# esp32-thing.net
KiCad netlist of a schematic drawn in EAGLE
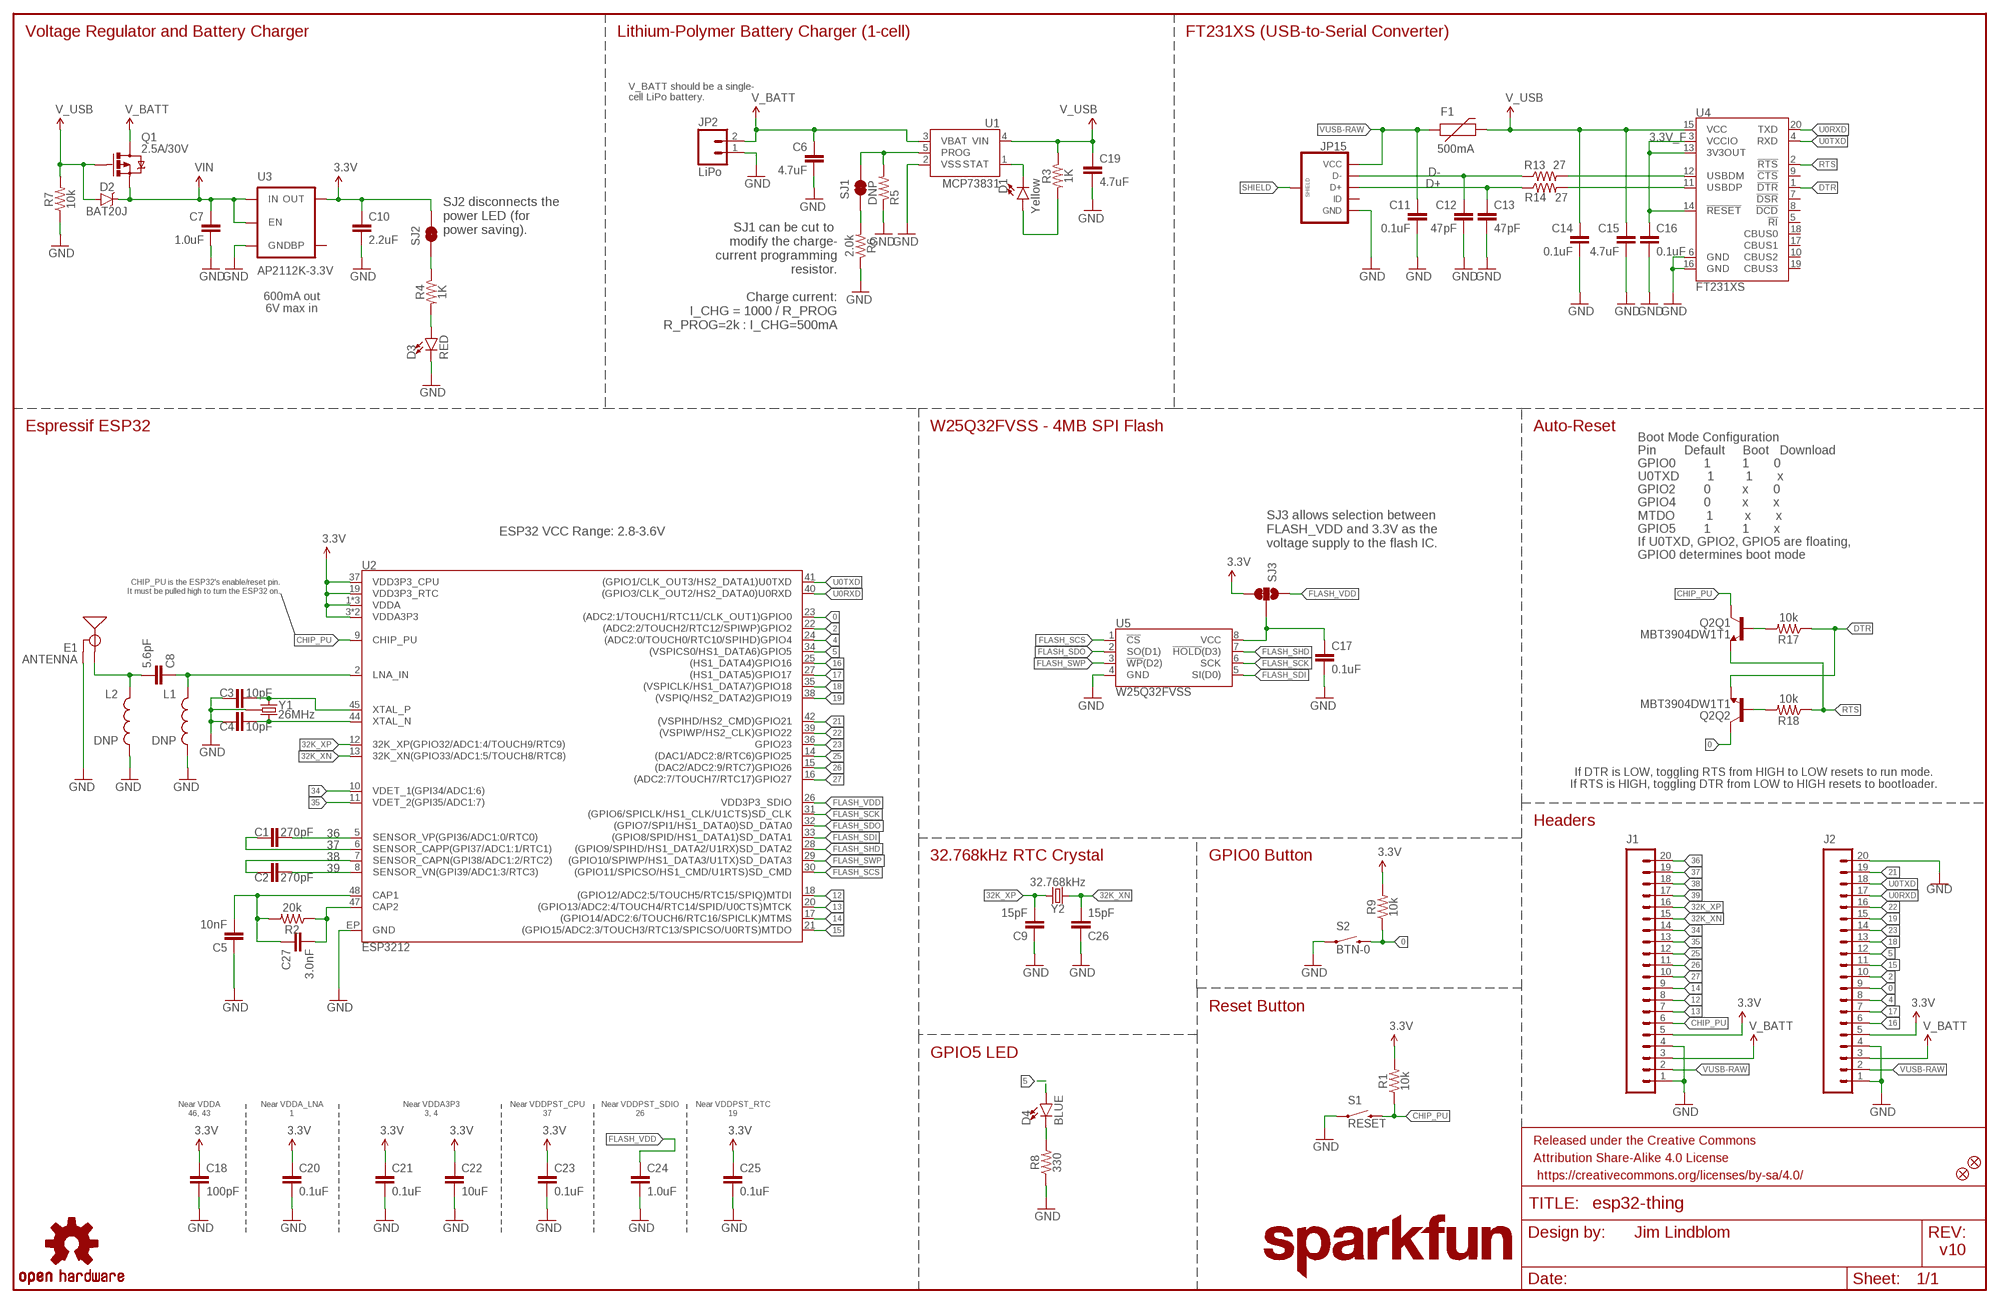
[diagram p0: schematic, sheet 1]

(export (version "E")
  (design (tool "Eeschema 10.0.6"))
  (components
    (comp (ref "C1")
      (value "270pF")
      (footprint "eagle-import:0603")
      (libsource (lib "eagle-import") (part "270PF-50V-5%(0603)"))
    )
    (comp (ref "C2")
      (value "270pF")
      (footprint "eagle-import:0603")
      (libsource (lib "eagle-import") (part "270PF-50V-5%(0603)"))
    )
    (comp (ref "C3")
      (value "10pF")
      (footprint "eagle-import:0603")
      (libsource (lib "eagle-import") (part "10PF-0603-50V-5%"))
    )
    (comp (ref "C4")
      (value "10pF")
      (footprint "eagle-import:0603")
      (libsource (lib "eagle-import") (part "10PF-0603-50V-5%"))
    )
    (comp (ref "C5")
      (value "10nF")
      (footprint "eagle-import:0603")
      (libsource (lib "eagle-import") (part "10NF-0603-50V-10%"))
    )
    (comp (ref "C6")
      (value "4.7uF")
      (footprint "eagle-import:0603")
      (libsource (lib "eagle-import") (part "4.7UF0603"))
    )
    (comp (ref "C7")
      (value "1.0uF")
      (footprint "eagle-import:0805")
      (libsource (lib "eagle-import") (part "1.0UF-0805-25V-(+80/-20%)"))
    )
    (comp (ref "C8")
      (value "5.6pF")
      (footprint "eagle-import:0603")
      (libsource (lib "eagle-import") (part "5.6PF-50V-5%(0603)"))
    )
    (comp (ref "C9")
      (value "15pF")
      (footprint "eagle-import:0603")
      (libsource (lib "eagle-import") (part "15PF-0603-50V-5%"))
    )
    (comp (ref "C10")
      (value "2.2uF")
      (footprint "eagle-import:0603")
      (libsource (lib "eagle-import") (part "2.2UF-0603-10V-20%"))
    )
    (comp (ref "C11")
      (value "0.1uF")
      (footprint "eagle-import:0603")
      (libsource (lib "eagle-import") (part "0.1UF-0603-25V-(+80/-20%)"))
    )
    (comp (ref "C12")
      (value "47pF")
      (footprint "eagle-import:0603")
      (libsource (lib "eagle-import") (part "47PF-0603-50V-5%"))
    )
    (comp (ref "C13")
      (value "47pF")
      (footprint "eagle-import:0603")
      (libsource (lib "eagle-import") (part "47PF-0603-50V-5%"))
    )
    (comp (ref "C14")
      (value "0.1uF")
      (footprint "eagle-import:0603")
      (libsource (lib "eagle-import") (part "0.1UF-0603-25V-(+80/-20%)"))
    )
    (comp (ref "C15")
      (value "4.7uF")
      (footprint "eagle-import:0603-CAP")
      (libsource (lib "eagle-import") (part "4.7UF-6.3V-10%(0603)0603"))
    )
    (comp (ref "C16")
      (value "0.1uF")
      (footprint "eagle-import:0603")
      (libsource (lib "eagle-import") (part "0.1UF-0603-25V-(+80/-20%)"))
    )
    (comp (ref "C17")
      (value "0.1uF")
      (footprint "eagle-import:0603")
      (libsource (lib "eagle-import") (part "0.1UF-0603-25V-(+80/-20%)"))
    )
    (comp (ref "C18")
      (value "100pF")
      (footprint "eagle-import:0603")
      (libsource (lib "eagle-import") (part "100PF-0603-50V-5%"))
    )
    (comp (ref "C19")
      (value "4.7uF")
      (footprint "eagle-import:0603")
      (libsource (lib "eagle-import") (part "4.7UF0603"))
    )
    (comp (ref "C20")
      (value "0.1uF")
      (footprint "eagle-import:0603")
      (libsource (lib "eagle-import") (part "0.1UF-0603-25V-(+80/-20%)"))
    )
    (comp (ref "C21")
      (value "0.1uF")
      (footprint "eagle-import:0603")
      (libsource (lib "eagle-import") (part "0.1UF-0603-25V-(+80/-20%)"))
    )
    (comp (ref "C22")
      (value "10uF")
      (footprint "eagle-import:0603")
      (libsource (lib "eagle-import") (part "10UF-0603-6.3V-20%"))
    )
    (comp (ref "C23")
      (value "0.1uF")
      (footprint "eagle-import:0603")
      (libsource (lib "eagle-import") (part "0.1UF-0603-25V-(+80/-20%)"))
    )
    (comp (ref "C24")
      (value "1.0uF")
      (footprint "eagle-import:0603")
      (libsource (lib "eagle-import") (part "1.0UF-0603-16V-10%"))
    )
    (comp (ref "C25")
      (value "0.1uF")
      (footprint "eagle-import:0603")
      (libsource (lib "eagle-import") (part "0.1UF-0603-25V-(+80/-20%)"))
    )
    (comp (ref "C26")
      (value "15pF")
      (footprint "eagle-import:0603")
      (libsource (lib "eagle-import") (part "15PF-0603-50V-5%"))
    )
    (comp (ref "C27")
      (value "3.0nF")
      (footprint "eagle-import:0603")
      (libsource (lib "eagle-import") (part "3.0NF-0603-50V-5%"))
    )
    (comp (ref "D1")
      (value "Yellow")
      (footprint "eagle-import:LED-0603")
      (libsource (lib "eagle-import") (part "LED-YELLOW0603"))
    )
    (comp (ref "D2")
      (value "BAT20J")
      (footprint "eagle-import:SOD-323")
      (libsource (lib "eagle-import") (part "DIODE-SCHOTTKY-BAT20J"))
    )
    (comp (ref "D3")
      (value "RED")
      (footprint "eagle-import:LED-0603")
      (libsource (lib "eagle-import") (part "LED-RED0603"))
    )
    (comp (ref "D4")
      (value "BLUE")
      (footprint "eagle-import:LED-0603")
      (libsource (lib "eagle-import") (part "LED-BLUE0603"))
    )
    (comp (ref "E1")
      (value "ANTENNA")
      (footprint "eagle-import:TRACE_ANTENNA_2.4GHZ_25.7MM_TUNED")
      (libsource (lib "eagle-import") (part "ANTENNATRACE-TUNED"))
    )
    (comp (ref "F1")
      (value "500mA")
      (footprint "eagle-import:PTC-1206")
      (libsource (lib "eagle-import") (part "PTCSMD"))
    )
    (comp (ref "FD1")
      (value "FIDUCIALUFIDUCIAL")
      (footprint "eagle-import:MICRO-FIDUCIAL")
      (libsource (lib "eagle-import") (part "FIDUCIALUFIDUCIAL"))
    )
    (comp (ref "FD2")
      (value "FIDUCIALUFIDUCIAL")
      (footprint "eagle-import:MICRO-FIDUCIAL")
      (libsource (lib "eagle-import") (part "FIDUCIALUFIDUCIAL"))
    )
    (comp (ref "FRAME1")
      (value "FRAME-LEDGER")
      (footprint "eagle-import:CREATIVE_COMMONS")
      (libsource (lib "eagle-import") (part "FRAME-LEDGER"))
    )
    (comp (ref "J1")
      (value "M20NOSILK")
      (footprint "eagle-import:1X20_NOSILK")
      (libsource (lib "eagle-import") (part "M20NOSILK"))
    )
    (comp (ref "J2")
      (value "M20NOSILK")
      (footprint "eagle-import:1X20_NOSILK")
      (libsource (lib "eagle-import") (part "M20NOSILK"))
    )
    (comp (ref "JP2")
      (value "LiPo")
      (footprint "eagle-import:JST-2-PTH")
      (libsource (lib "eagle-import") (part "M02JST-PTH-2"))
    )
    (comp (ref "JP15")
      (value "USB_MICROB_PLUGCONN-11752")
      (footprint "eagle-import:USB-B-MICRO-SMD_V03")
      (libsource (lib "eagle-import") (part "USB_MICROB_PLUGCONN-11752"))
    )
    (comp (ref "L1")
      (value "DNP")
      (footprint "eagle-import:0603")
      (libsource (lib "eagle-import") (part "INDUCTOR0603"))
    )
    (comp (ref "L2")
      (value "DNP")
      (footprint "eagle-import:0603")
      (libsource (lib "eagle-import") (part "INDUCTOR0603"))
    )
    (comp (ref "LOGO1")
      (value "SFE_LOGO_NAME.2_INCH")
      (footprint "eagle-import:SFE_LOGO_NAME_.2")
      (libsource (lib "eagle-import") (part "SFE_LOGO_NAME.2_INCH"))
    )
    (comp (ref "LOGO2")
      (value "OSHW-LOGOMINI")
      (footprint "eagle-import:OSHW-LOGO-MINI")
      (libsource (lib "eagle-import") (part "OSHW-LOGOMINI"))
    )
    (comp (ref "LOGO3")
      (value "SFE_LOGO_NAME.2_INCH")
      (footprint "eagle-import:SFE_LOGO_NAME_.2")
      (libsource (lib "eagle-import") (part "SFE_LOGO_NAME.2_INCH"))
    )
    (comp (ref "Q1")
      (value "2.5A/30V")
      (footprint "eagle-import:SOT23-3")
      (libsource (lib "eagle-import") (part "MOSFET-PCHANNELDMG2307L"))
    )
    (comp (ref "Q2")
      (value "MBT3904DW1T1")
      (footprint "eagle-import:SC70-6")
      (libsource (lib "eagle-import") (part "MBT3904DW1T1"))
    )
    (comp (ref "R1")
      (value "10k")
      (footprint "eagle-import:0603")
      (libsource (lib "eagle-import") (part "10KOHM-1/10W-1%(0603)0603"))
    )
    (comp (ref "R2")
      (value "20k")
      (footprint "eagle-import:0603")
      (libsource (lib "eagle-import") (part "20KOHM-0603-1/10W-1%"))
    )
    (comp (ref "R3")
      (value "1K")
      (footprint "eagle-import:0603")
      (libsource (lib "eagle-import") (part "1KOHM-1/10W-1%(0603)"))
    )
    (comp (ref "R4")
      (value "1K")
      (footprint "eagle-import:0603")
      (libsource (lib "eagle-import") (part "1KOHM-1/10W-1%(0603)"))
    )
    (comp (ref "R5")
      (value "DNP")
      (footprint "eagle-import:1_6W-RES")
      (libsource (lib "eagle-import") (part "RESISTORPTH-1/6W"))
    )
    (comp (ref "R6")
      (value "2.0k")
      (footprint "eagle-import:0603")
      (libsource (lib "eagle-import") (part "2.0KOHM1/10W5%(0603)"))
    )
    (comp (ref "R7")
      (value "10k")
      (footprint "eagle-import:0603")
      (libsource (lib "eagle-import") (part "10KOHM-0603-1/10W-1%"))
    )
    (comp (ref "R8")
      (value "330")
      (footprint "eagle-import:0603")
      (libsource (lib "eagle-import") (part "330OHM1/10W1%(0603)"))
    )
    (comp (ref "R9")
      (value "10k")
      (footprint "eagle-import:0603")
      (libsource (lib "eagle-import") (part "10KOHM-1/10W-1%(0603)0603"))
    )
    (comp (ref "R13")
      (value "27")
      (footprint "eagle-import:0603")
      (libsource (lib "eagle-import") (part "27OHM1/10W1%(0603)0603-RES"))
    )
    (comp (ref "R14")
      (value "27")
      (footprint "eagle-import:0603")
      (libsource (lib "eagle-import") (part "27OHM1/10W1%(0603)0603-RES"))
    )
    (comp (ref "R17")
      (value "10k")
      (footprint "eagle-import:0603")
      (libsource (lib "eagle-import") (part "10KOHM-0603-1/10W-1%"))
    )
    (comp (ref "R18")
      (value "10k")
      (footprint "eagle-import:0603")
      (libsource (lib "eagle-import") (part "10KOHM-0603-1/10W-1%"))
    )
    (comp (ref "S1")
      (value "RESET")
      (footprint "eagle-import:TACTILE_SWITCH_SMD_4.6X2.8MM")
      (libsource (lib "eagle-import") (part "SWITCH-MOMENTARY-2SMD-4.6X2.8MM"))
    )
    (comp (ref "S2")
      (value "BTN-0")
      (footprint "eagle-import:TACTILE_SWITCH_SMD_4.6X2.8MM")
      (libsource (lib "eagle-import") (part "SWITCH-MOMENTARY-2SMD-4.6X2.8MM"))
    )
    (comp (ref "SJ1")
      (value "JUMPER-PAD-2-NC_BY_TRACE")
      (footprint "eagle-import:PAD-JUMPER-2-NC_BY_TRACE_YES_SILK")
      (libsource (lib "eagle-import") (part "JUMPER-PAD-2-NC_BY_TRACE"))
    )
    (comp (ref "SJ2")
      (value "JUMPER-PAD-2-NC_BY_TRACE")
      (footprint "eagle-import:PAD-JUMPER-2-NC_BY_TRACE_YES_SILK")
      (libsource (lib "eagle-import") (part "JUMPER-PAD-2-NC_BY_TRACE"))
    )
    (comp (ref "SJ3")
      (value "JUMPER-PAD-3-2OF3_NC_BY_TRACE_SMALL")
      (footprint "eagle-import:PAD-JUMPER-3-2OF3_NC_BY_TRACE_YES_SILK_FULL_BOX")
      (libsource (lib "eagle-import") (part "JUMPER-PAD-3-2OF3_NC_BY_TRACE_SMALL"))
    )
    (comp (ref "U1")
      (value "MCP73831")
      (footprint "eagle-import:SOT23-5")
      (libsource (lib "eagle-import") (part "MCP73831"))
    )
    (comp (ref "U2")
      (value "ESP3212")
      (footprint "eagle-import:QFN48-0.4MM")
      (libsource (lib "eagle-import") (part "ESP3212"))
    )
    (comp (ref "U3")
      (value "AP2112K-3.3V")
      (footprint "eagle-import:SOT23-5")
      (libsource (lib "eagle-import") (part "V_REG_LDOSMD"))
    )
    (comp (ref "U4")
      (value "FT231XS")
      (footprint "eagle-import:SSOP20_L")
      (libsource (lib "eagle-import") (part "FT231XS"))
    )
    (comp (ref "U5")
      (value "W25Q32FVSS")
      (footprint "eagle-import:SOIC-8")
      (libsource (lib "eagle-import") (part "W25Q32FVSS"))
    )
    (comp (ref "Y1")
      (value "26MHz")
      (footprint "eagle-import:CRYSTAL-SMD-3.2X2.5")
      (libsource (lib "eagle-import") (part "CRYSTAL-GROUNDED3.2X2.5"))
    )
    (comp (ref "Y2")
      (value "32.768kHz")
      (footprint "eagle-import:CRYSTAL-SMD-3.2X1.5MM")
      (libsource (lib "eagle-import") (part "CRYSTAL-32.768KHZSMD-3.2X1.5"))
    )
  )
  (nets
    (net (code "1") (name "/3.3V_F") (class "Default")
      (node (ref "C16") (pin "1") (pinfunction "1_1") (pintype "passive"))
      (node (ref "U4") (pin "13") (pinfunction "3V3OUT_13") (pintype "bidirectional"))
      (node (ref "U4") (pin "14") (pinfunction "~{RESET}_14") (pintype "bidirectional"))
      (node (ref "U4") (pin "3") (pinfunction "VCCIO_3") (pintype "bidirectional"))
    )
    (net (code "2") (name "/D+") (class "Default")
      (node (ref "C13") (pin "1") (pinfunction "1_1") (pintype "passive"))
      (node (ref "JP15") (pin "D+") (pinfunction "D+_D+") (pintype "bidirectional"))
      (node (ref "R14") (pin "1") (pinfunction "1_1") (pintype "passive"))
    )
    (net (code "3") (name "/D-") (class "Default")
      (node (ref "C12") (pin "1") (pinfunction "1_1") (pintype "passive"))
      (node (ref "JP15") (pin "D-") (pinfunction "D-_D-") (pintype "bidirectional"))
      (node (ref "R13") (pin "1") (pinfunction "1_1") (pintype "passive"))
    )
    (net (code "4") (name "0") (class "Default")
      (node (ref "J2") (pin "9") (pinfunction "9_9") (pintype "passive"))
      (node (ref "Q2") (pin "6") (pinfunction "C_6") (pintype "passive"))
      (node (ref "R9") (pin "1") (pinfunction "1_1") (pintype "passive"))
      (node (ref "S2") (pin "3") (pinfunction "2_3") (pintype "passive"))
      (node (ref "S2") (pin "4") (pinfunction "2_4") (pintype "passive"))
      (node (ref "U2") (pin "23") (pinfunction "(ADC2:1/TOUCH1/RTC11/CLK_OUT1)GPIO0_23") (pintype "bidirectional"))
    )
    (net (code "5") (name "2") (class "Default")
      (node (ref "J2") (pin "10") (pinfunction "10_10") (pintype "passive"))
      (node (ref "U2") (pin "22") (pinfunction "(ADC2:2/TOUCH2/RTC12/SPIWP)GPIO2_22") (pintype "bidirectional"))
    )
    (net (code "6") (name "3.3V") (class "Default")
      (node (ref "C10") (pin "1") (pinfunction "1_1") (pintype "passive"))
      (node (ref "C18") (pin "1") (pinfunction "1_1") (pintype "passive"))
      (node (ref "C20") (pin "1") (pinfunction "1_1") (pintype "passive"))
      (node (ref "C21") (pin "1") (pinfunction "1_1") (pintype "passive"))
      (node (ref "C22") (pin "1") (pinfunction "1_1") (pintype "passive"))
      (node (ref "C23") (pin "1") (pinfunction "1_1") (pintype "passive"))
      (node (ref "C25") (pin "1") (pinfunction "1_1") (pintype "passive"))
      (node (ref "J1") (pin "5") (pinfunction "5_5") (pintype "passive"))
      (node (ref "J2") (pin "5") (pinfunction "5_5") (pintype "passive"))
      (node (ref "R1") (pin "2") (pinfunction "2_2") (pintype "passive"))
      (node (ref "R9") (pin "2") (pinfunction "2_2") (pintype "passive"))
      (node (ref "SJ2") (pin "2") (pinfunction "2_2") (pintype "passive"))
      (node (ref "SJ3") (pin "3") (pinfunction "3_3") (pintype "passive"))
      (node (ref "U2") (pin "1") (pinfunction "VDDA_1") (pintype "bidirectional"))
      (node (ref "U2") (pin "19") (pinfunction "VDD3P3_RTC_19") (pintype "bidirectional"))
      (node (ref "U2") (pin "3") (pinfunction "VDDA3P3_3") (pintype "bidirectional"))
      (node (ref "U2") (pin "37") (pinfunction "VDD3P3_CPU_37") (pintype "bidirectional"))
      (node (ref "U2") (pin "4") (pinfunction "VDDA3P3_4") (pintype "bidirectional"))
      (node (ref "U2") (pin "43") (pinfunction "VDDA_43") (pintype "bidirectional"))
      (node (ref "U2") (pin "46") (pinfunction "VDDA_46") (pintype "bidirectional"))
      (node (ref "U3") (pin "5") (pinfunction "OUT_5") (pintype "passive"))
    )
    (net (code "7") (name "4") (class "Default")
      (node (ref "J2") (pin "8") (pinfunction "8_8") (pintype "passive"))
      (node (ref "U2") (pin "24") (pinfunction "(ADC2:0/TOUCH0/RTC10/SPIHD)GPIO4_24") (pintype "bidirectional"))
    )
    (net (code "8") (name "5") (class "Default")
      (node (ref "D4") (pin "A") (pinfunction "A_A") (pintype "passive"))
      (node (ref "J2") (pin "12") (pinfunction "12_12") (pintype "passive"))
      (node (ref "U2") (pin "34") (pinfunction "(VSPICS0/HS1_DATA6)GPIO5_34") (pintype "bidirectional"))
    )
    (net (code "9") (name "12") (class "Default")
      (node (ref "J1") (pin "8") (pinfunction "8_8") (pintype "passive"))
      (node (ref "U2") (pin "18") (pinfunction "(GPIO12/ADC2:5/TOUCH5/RTC15/SPIQ)MTDI_18") (pintype "bidirectional"))
    )
    (net (code "10") (name "13") (class "Default")
      (node (ref "J1") (pin "7") (pinfunction "7_7") (pintype "passive"))
      (node (ref "U2") (pin "20") (pinfunction "(GPIO13/ADC2:4/TOUCH4/RTC14/SPID/U0CTS)MTCK_20") (pintype "bidirectional"))
    )
    (net (code "11") (name "14") (class "Default")
      (node (ref "J1") (pin "9") (pinfunction "9_9") (pintype "passive"))
      (node (ref "U2") (pin "17") (pinfunction "(GPIO14/ADC2:6/TOUCH6/RTC16/SPICLK)MTMS_17") (pintype "bidirectional"))
    )
    (net (code "12") (name "15") (class "Default")
      (node (ref "J2") (pin "11") (pinfunction "11_11") (pintype "passive"))
      (node (ref "U2") (pin "21") (pinfunction "(GPIO15/ADC2:3/TOUCH3/RTC13/SPICSO/U0RTS)MTDO_21") (pintype "bidirectional"))
    )
    (net (code "13") (name "16") (class "Default")
      (node (ref "J2") (pin "6") (pinfunction "6_6") (pintype "passive"))
      (node (ref "U2") (pin "25") (pinfunction "(HS1_DATA4)GPIO16_25") (pintype "bidirectional"))
    )
    (net (code "14") (name "17") (class "Default")
      (node (ref "J2") (pin "7") (pinfunction "7_7") (pintype "passive"))
      (node (ref "U2") (pin "27") (pinfunction "(HS1_DATA5)GPIO17_27") (pintype "bidirectional"))
    )
    (net (code "15") (name "18") (class "Default")
      (node (ref "J2") (pin "13") (pinfunction "13_13") (pintype "passive"))
      (node (ref "U2") (pin "35") (pinfunction "(VSPICLK/HS1_DATA7)GPIO18_35") (pintype "bidirectional"))
    )
    (net (code "16") (name "19") (class "Default")
      (node (ref "J2") (pin "15") (pinfunction "15_15") (pintype "passive"))
      (node (ref "U2") (pin "38") (pinfunction "(VSPIQ/HS2_DATA2)GPIO19_38") (pintype "bidirectional"))
    )
    (net (code "17") (name "21") (class "Default")
      (node (ref "J2") (pin "19") (pinfunction "19_19") (pintype "passive"))
      (node (ref "U2") (pin "42") (pinfunction "(VSPIHD/HS2_CMD)GPIO21_42") (pintype "bidirectional"))
    )
    (net (code "18") (name "22") (class "Default")
      (node (ref "J2") (pin "16") (pinfunction "16_16") (pintype "passive"))
      (node (ref "U2") (pin "39") (pinfunction "(VSPIWP/HS2_CLK)GPIO22_39") (pintype "bidirectional"))
    )
    (net (code "19") (name "23") (class "Default")
      (node (ref "J2") (pin "14") (pinfunction "14_14") (pintype "passive"))
      (node (ref "U2") (pin "36") (pinfunction "GPIO23_36") (pintype "bidirectional"))
    )
    (net (code "20") (name "25") (class "Default")
      (node (ref "J1") (pin "12") (pinfunction "12_12") (pintype "passive"))
      (node (ref "U2") (pin "14") (pinfunction "(DAC1/ADC2:8/RTC6)GPIO25_14") (pintype "bidirectional"))
    )
    (net (code "21") (name "26") (class "Default")
      (node (ref "J1") (pin "11") (pinfunction "11_11") (pintype "passive"))
      (node (ref "U2") (pin "15") (pinfunction "(DAC2/ADC2:9/RTC7)GPIO26_15") (pintype "bidirectional"))
    )
    (net (code "22") (name "27") (class "Default")
      (node (ref "J1") (pin "10") (pinfunction "10_10") (pintype "passive"))
      (node (ref "U2") (pin "16") (pinfunction "(ADC2:7/TOUCH7/RTC17)GPIO27_16") (pintype "bidirectional"))
    )
    (net (code "23") (name "32K_XN") (class "Default")
      (node (ref "C26") (pin "2") (pinfunction "2_2") (pintype "passive"))
      (node (ref "J1") (pin "15") (pinfunction "15_15") (pintype "passive"))
      (node (ref "U2") (pin "13") (pinfunction "32K_XN(GPIO33/ADC1:5/TOUCH8/RTC8)_13") (pintype "bidirectional"))
      (node (ref "Y2") (pin "P$2") (pinfunction "2_P$2") (pintype "passive"))
    )
    (net (code "24") (name "32K_XP") (class "Default")
      (node (ref "C9") (pin "2") (pinfunction "2_2") (pintype "passive"))
      (node (ref "J1") (pin "16") (pinfunction "16_16") (pintype "passive"))
      (node (ref "U2") (pin "12") (pinfunction "32K_XP(GPIO32/ADC1:4/TOUCH9/RTC9)_12") (pintype "bidirectional"))
      (node (ref "Y2") (pin "P$1") (pinfunction "1_P$1") (pintype "passive"))
    )
    (net (code "25") (name "34") (class "Default")
      (node (ref "J1") (pin "14") (pinfunction "14_14") (pintype "passive"))
      (node (ref "U2") (pin "10") (pinfunction "VDET_1(GPI34/ADC1:6)_10") (pintype "bidirectional"))
    )
    (net (code "26") (name "35") (class "Default")
      (node (ref "J1") (pin "13") (pinfunction "13_13") (pintype "passive"))
      (node (ref "U2") (pin "11") (pinfunction "VDET_2(GPI35/ADC1:7)_11") (pintype "bidirectional"))
    )
    (net (code "27") (name "36") (class "Default")
      (node (ref "C1") (pin "2") (pinfunction "2_2") (pintype "passive"))
      (node (ref "J1") (pin "20") (pinfunction "20_20") (pintype "passive"))
      (node (ref "U2") (pin "5") (pinfunction "SENSOR_VP(GPI36/ADC1:0/RTC0)_5") (pintype "bidirectional"))
    )
    (net (code "28") (name "37") (class "Default")
      (node (ref "C1") (pin "1") (pinfunction "1_1") (pintype "passive"))
      (node (ref "J1") (pin "19") (pinfunction "19_19") (pintype "passive"))
      (node (ref "U2") (pin "6") (pinfunction "SENSOR_CAPP(GPI37/ADC1:1/RTC1)_6") (pintype "bidirectional"))
    )
    (net (code "29") (name "38") (class "Default")
      (node (ref "C2") (pin "1") (pinfunction "1_1") (pintype "passive"))
      (node (ref "J1") (pin "18") (pinfunction "18_18") (pintype "passive"))
      (node (ref "U2") (pin "7") (pinfunction "SENSOR_CAPN(GPI38/ADC1:2/RTC2)_7") (pintype "bidirectional"))
    )
    (net (code "30") (name "39") (class "Default")
      (node (ref "C2") (pin "2") (pinfunction "2_2") (pintype "passive"))
      (node (ref "J1") (pin "17") (pinfunction "17_17") (pintype "passive"))
      (node (ref "U2") (pin "8") (pinfunction "SENSOR_VN(GPI39/ADC1:3/RTC3)_8") (pintype "bidirectional"))
    )
    (net (code "31") (name "CHIP_PU") (class "Default")
      (node (ref "J1") (pin "6") (pinfunction "6_6") (pintype "passive"))
      (node (ref "Q2") (pin "3") (pinfunction "C_3") (pintype "passive"))
      (node (ref "R1") (pin "1") (pinfunction "1_1") (pintype "passive"))
      (node (ref "S1") (pin "3") (pinfunction "2_3") (pintype "passive"))
      (node (ref "S1") (pin "4") (pinfunction "2_4") (pintype "passive"))
      (node (ref "U2") (pin "9") (pinfunction "CHIP_PU_9") (pintype "bidirectional"))
    )
    (net (code "32") (name "DTR") (class "Default")
      (node (ref "Q2") (pin "1") (pinfunction "E_1") (pintype "passive"))
      (node (ref "R17") (pin "1") (pinfunction "1_1") (pintype "passive"))
      (node (ref "U4") (pin "1") (pinfunction "~{DTR}_1") (pintype "bidirectional"))
    )
    (net (code "33") (name "FLASH_SCK") (class "Default")
      (node (ref "U2") (pin "31") (pinfunction "(GPIO6/SPICLK/HS1_CLK/U1CTS)SD_CLK_31") (pintype "bidirectional"))
      (node (ref "U5") (pin "6") (pinfunction "SCK_6") (pintype "bidirectional"))
    )
    (net (code "34") (name "FLASH_SCS") (class "Default")
      (node (ref "U2") (pin "30") (pinfunction "(GPIO11/SPICSO/HS1_CMD/U1RTS)SD_CMD_30") (pintype "bidirectional"))
      (node (ref "U5") (pin "1") (pinfunction "~{CS}_1") (pintype "bidirectional"))
    )
    (net (code "35") (name "FLASH_SDI") (class "Default")
      (node (ref "U2") (pin "33") (pinfunction "(GPIO8/SPID/HS1_DATA1)SD_DATA1_33") (pintype "bidirectional"))
      (node (ref "U5") (pin "5") (pinfunction "SI(D0)_5") (pintype "bidirectional"))
    )
    (net (code "36") (name "FLASH_SDO") (class "Default")
      (node (ref "U2") (pin "32") (pinfunction "(GPIO7/SPI1/HS1_DATA0)SD_DATA0_32") (pintype "bidirectional"))
      (node (ref "U5") (pin "2") (pinfunction "SO(D1)_2") (pintype "bidirectional"))
    )
    (net (code "37") (name "FLASH_SHD") (class "Default")
      (node (ref "U2") (pin "28") (pinfunction "(GPIO9/SPIHD/HS1_DATA2/U1RX)SD_DATA2_28") (pintype "bidirectional"))
      (node (ref "U5") (pin "7") (pinfunction "~{HOLD}(D3)_7") (pintype "bidirectional"))
    )
    (net (code "38") (name "FLASH_SWP") (class "Default")
      (node (ref "U2") (pin "29") (pinfunction "(GPIO10/SPIWP/HS1_DATA3/U1TX)SD_DATA3_29") (pintype "bidirectional"))
      (node (ref "U5") (pin "3") (pinfunction "~{WP}(D2)_3") (pintype "bidirectional"))
    )
    (net (code "39") (name "FLASH_VDD") (class "Default")
      (node (ref "C24") (pin "1") (pinfunction "1_1") (pintype "passive"))
      (node (ref "SJ3") (pin "1") (pinfunction "1_1") (pintype "passive"))
      (node (ref "U2") (pin "26") (pinfunction "VDD3P3_SDIO_26") (pintype "bidirectional"))
    )
    (net (code "40") (name "GND") (class "Default")
      (node (ref "C10") (pin "2") (pinfunction "2_2") (pintype "passive"))
      (node (ref "C11") (pin "2") (pinfunction "2_2") (pintype "passive"))
      (node (ref "C12") (pin "2") (pinfunction "2_2") (pintype "passive"))
      (node (ref "C13") (pin "2") (pinfunction "2_2") (pintype "passive"))
      (node (ref "C14") (pin "2") (pinfunction "2_2") (pintype "passive"))
      (node (ref "C15") (pin "2") (pinfunction "2_2") (pintype "passive"))
      (node (ref "C16") (pin "2") (pinfunction "2_2") (pintype "passive"))
      (node (ref "C17") (pin "2") (pinfunction "2_2") (pintype "passive"))
      (node (ref "C18") (pin "2") (pinfunction "2_2") (pintype "passive"))
      (node (ref "C19") (pin "2") (pinfunction "2_2") (pintype "passive"))
      (node (ref "C20") (pin "2") (pinfunction "2_2") (pintype "passive"))
      (node (ref "C21") (pin "2") (pinfunction "2_2") (pintype "passive"))
      (node (ref "C22") (pin "2") (pinfunction "2_2") (pintype "passive"))
      (node (ref "C23") (pin "2") (pinfunction "2_2") (pintype "passive"))
      (node (ref "C24") (pin "2") (pinfunction "2_2") (pintype "passive"))
      (node (ref "C25") (pin "2") (pinfunction "2_2") (pintype "passive"))
      (node (ref "C26") (pin "1") (pinfunction "1_1") (pintype "passive"))
      (node (ref "C3") (pin "1") (pinfunction "1_1") (pintype "passive"))
      (node (ref "C4") (pin "1") (pinfunction "1_1") (pintype "passive"))
      (node (ref "C5") (pin "1") (pinfunction "1_1") (pintype "passive"))
      (node (ref "C6") (pin "2") (pinfunction "2_2") (pintype "passive"))
      (node (ref "C7") (pin "2") (pinfunction "2_2") (pintype "passive"))
      (node (ref "C9") (pin "1") (pinfunction "1_1") (pintype "passive"))
      (node (ref "D3") (pin "C") (pinfunction "C_C") (pintype "passive"))
      (node (ref "E1") (pin "GND") (pinfunction "GND_GND") (pintype "bidirectional"))
      (node (ref "E1") (pin "GND2") (pinfunction "GND_GND2") (pintype "bidirectional"))
      (node (ref "J1") (pin "1") (pinfunction "1_1") (pintype "passive"))
      (node (ref "J1") (pin "4") (pinfunction "4_4") (pintype "passive"))
      (node (ref "J2") (pin "1") (pinfunction "1_1") (pintype "passive"))
      (node (ref "J2") (pin "20") (pinfunction "20_20") (pintype "passive"))
      (node (ref "J2") (pin "4") (pinfunction "4_4") (pintype "passive"))
      (node (ref "JP15") (pin "GND") (pinfunction "GND_GND") (pintype "bidirectional"))
      (node (ref "JP2") (pin "1") (pinfunction "1_1") (pintype "passive"))
      (node (ref "L1") (pin "2") (pinfunction "2_2") (pintype "passive"))
      (node (ref "L2") (pin "2") (pinfunction "2_2") (pintype "passive"))
      (node (ref "R5") (pin "1") (pinfunction "1_1") (pintype "passive"))
      (node (ref "R6") (pin "1") (pinfunction "1_1") (pintype "passive"))
      (node (ref "R7") (pin "1") (pinfunction "1_1") (pintype "passive"))
      (node (ref "R8") (pin "1") (pinfunction "1_1") (pintype "passive"))
      (node (ref "S1") (pin "1") (pinfunction "1_1") (pintype "passive"))
      (node (ref "S1") (pin "2") (pinfunction "1_2") (pintype "passive"))
      (node (ref "S2") (pin "1") (pinfunction "1_1") (pintype "passive"))
      (node (ref "S2") (pin "2") (pinfunction "1_2") (pintype "passive"))
      (node (ref "U1") (pin "2") (pinfunction "VSS_2") (pintype "power_in"))
      (node (ref "U2") (pin "EP") (pinfunction "GND_EP") (pintype "bidirectional"))
      (node (ref "U3") (pin "2") (pinfunction "GND_2") (pintype "input"))
      (node (ref "U4") (pin "16") (pinfunction "GND_16") (pintype "bidirectional"))
      (node (ref "U4") (pin "6") (pinfunction "GND_6") (pintype "bidirectional"))
      (node (ref "U5") (pin "4") (pinfunction "GND_4") (pintype "bidirectional"))
      (node (ref "Y1") (pin "2") (pinfunction "GND_2") (pintype "passive"))
      (node (ref "Y1") (pin "4") (pinfunction "GND_4") (pintype "passive"))
    )
    (net (code "41") (name "Net-(D1-PadA)") (class "Default")
      (node (ref "D1") (pin "A") (pinfunction "A_A") (pintype "passive"))
      (node (ref "R3") (pin "2") (pinfunction "2_2") (pintype "passive"))
    )
    (net (code "42") (name "Net-(D3-PadA)") (class "Default")
      (node (ref "D3") (pin "A") (pinfunction "A_A") (pintype "passive"))
      (node (ref "R4") (pin "2") (pinfunction "2_2") (pintype "passive"))
    )
    (net (code "43") (name "Net-(D4-PadC)") (class "Default")
      (node (ref "D4") (pin "C") (pinfunction "C_C") (pintype "passive"))
      (node (ref "R8") (pin "2") (pinfunction "2_2") (pintype "passive"))
    )
    (net (code "44") (name "Net-(E1-SIGNAL)") (class "Default")
      (node (ref "C8") (pin "2") (pinfunction "2_2") (pintype "passive"))
      (node (ref "E1") (pin "ANT") (pinfunction "SIGNAL_ANT") (pintype "bidirectional"))
      (node (ref "L2") (pin "1") (pinfunction "1_1") (pintype "passive"))
    )
    (net (code "45") (name "Net-(Q2A-B)") (class "Default")
      (node (ref "Q2") (pin "5") (pinfunction "B_5") (pintype "passive"))
      (node (ref "R17") (pin "2") (pinfunction "2_2") (pintype "passive"))
    )
    (net (code "46") (name "Net-(Q2B-B)") (class "Default")
      (node (ref "Q2") (pin "2") (pinfunction "B_2") (pintype "passive"))
      (node (ref "R18") (pin "2") (pinfunction "2_2") (pintype "passive"))
    )
    (net (code "47") (name "Net-(R4-Pad1)") (class "Default")
      (node (ref "R4") (pin "1") (pinfunction "1_1") (pintype "passive"))
      (node (ref "SJ2") (pin "1") (pinfunction "1_1") (pintype "passive"))
    )
    (net (code "48") (name "Net-(R6-Pad2)") (class "Default")
      (node (ref "R6") (pin "2") (pinfunction "2_2") (pintype "passive"))
      (node (ref "SJ1") (pin "1") (pinfunction "1_1") (pintype "passive"))
    )
    (net (code "49") (name "Net-(U1-PROG)") (class "Default")
      (node (ref "R5") (pin "2") (pinfunction "2_2") (pintype "passive"))
      (node (ref "SJ1") (pin "2") (pinfunction "2_2") (pintype "passive"))
      (node (ref "U1") (pin "5") (pinfunction "PROG_5") (pintype "input"))
    )
    (net (code "50") (name "Net-(U1-STAT)") (class "Default")
      (node (ref "D1") (pin "C") (pinfunction "C_C") (pintype "passive"))
      (node (ref "U1") (pin "1") (pinfunction "STAT_1") (pintype "output"))
    )
    (net (code "51") (name "Net-(U2-CAP1)") (class "Default")
      (node (ref "C27") (pin "1") (pinfunction "1_1") (pintype "passive"))
      (node (ref "C5") (pin "2") (pinfunction "2_2") (pintype "passive"))
      (node (ref "R2") (pin "2") (pinfunction "2_2") (pintype "passive"))
      (node (ref "U2") (pin "48") (pinfunction "CAP1_48") (pintype "bidirectional"))
    )
    (net (code "52") (name "Net-(U2-CAP2)") (class "Default")
      (node (ref "C27") (pin "2") (pinfunction "2_2") (pintype "passive"))
      (node (ref "R2") (pin "1") (pinfunction "1_1") (pintype "passive"))
      (node (ref "U2") (pin "47") (pinfunction "CAP2_47") (pintype "bidirectional"))
    )
    (net (code "53") (name "Net-(U2-LNA_IN)") (class "Default")
      (node (ref "C8") (pin "1") (pinfunction "1_1") (pintype "passive"))
      (node (ref "L1") (pin "1") (pinfunction "1_1") (pintype "passive"))
      (node (ref "U2") (pin "2") (pinfunction "LNA_IN_2") (pintype "bidirectional"))
    )
    (net (code "54") (name "Net-(U2-XTAL_N)") (class "Default")
      (node (ref "C4") (pin "2") (pinfunction "2_2") (pintype "passive"))
      (node (ref "U2") (pin "44") (pinfunction "XTAL_N_44") (pintype "bidirectional"))
      (node (ref "Y1") (pin "3") (pinfunction "2_3") (pintype "passive"))
    )
    (net (code "55") (name "Net-(U2-XTAL_P)") (class "Default")
      (node (ref "C3") (pin "2") (pinfunction "2_2") (pintype "passive"))
      (node (ref "U2") (pin "45") (pinfunction "XTAL_P_45") (pintype "bidirectional"))
      (node (ref "Y1") (pin "1") (pinfunction "1_1") (pintype "passive"))
    )
    (net (code "56") (name "Net-(U4-USBDM)") (class "Default")
      (node (ref "R13") (pin "2") (pinfunction "2_2") (pintype "passive"))
      (node (ref "U4") (pin "12") (pinfunction "USBDM_12") (pintype "bidirectional"))
    )
    (net (code "57") (name "Net-(U4-USBDP)") (class "Default")
      (node (ref "R14") (pin "2") (pinfunction "2_2") (pintype "passive"))
      (node (ref "U4") (pin "11") (pinfunction "USBDP_11") (pintype "bidirectional"))
    )
    (net (code "58") (name "Net-(U5-VCC)") (class "Default")
      (node (ref "C17") (pin "1") (pinfunction "1_1") (pintype "passive"))
      (node (ref "SJ3") (pin "2") (pinfunction "2_2") (pintype "passive"))
      (node (ref "U5") (pin "8") (pinfunction "VCC_8") (pintype "bidirectional"))
    )
    (net (code "59") (name "RTS") (class "Default")
      (node (ref "Q2") (pin "4") (pinfunction "E_4") (pintype "passive"))
      (node (ref "R18") (pin "1") (pinfunction "1_1") (pintype "passive"))
      (node (ref "U4") (pin "2") (pinfunction "~{RTS}_2") (pintype "bidirectional"))
    )
    (net (code "60") (name "SHIELD") (class "Default")
      (node (ref "JP15") (pin "SHIELD1") (pinfunction "SHIELD_SHIELD1") (pintype "bidirectional"))
      (node (ref "JP15") (pin "SHIELD2") (pinfunction "SHIELD_SHIELD2") (pintype "bidirectional"))
      (node (ref "JP15") (pin "SHIELD3") (pinfunction "SHIELD_SHIELD3") (pintype "bidirectional"))
    )
    (net (code "61") (name "U0RXD") (class "Default")
      (node (ref "J2") (pin "17") (pinfunction "17_17") (pintype "passive"))
      (node (ref "U2") (pin "40") (pinfunction "(GPIO3/CLK_OUT2/HS2_DATA0)U0RXD_40") (pintype "bidirectional"))
      (node (ref "U4") (pin "20") (pinfunction "TXD_20") (pintype "bidirectional"))
    )
    (net (code "62") (name "U0TXD") (class "Default")
      (node (ref "J2") (pin "18") (pinfunction "18_18") (pintype "passive"))
      (node (ref "U2") (pin "41") (pinfunction "(GPIO1/CLK_OUT3/HS2_DATA1)U0TXD_41") (pintype "bidirectional"))
      (node (ref "U4") (pin "4") (pinfunction "RXD_4") (pintype "bidirectional"))
    )
    (net (code "63") (name "VIN") (class "Default")
      (node (ref "C7") (pin "1") (pinfunction "1_1") (pintype "passive"))
      (node (ref "D2") (pin "C") (pinfunction "C_C") (pintype "passive"))
      (node (ref "Q1") (pin "2") (pinfunction "S_2") (pintype "passive"))
      (node (ref "U3") (pin "1") (pinfunction "IN_1") (pintype "input"))
      (node (ref "U3") (pin "3") (pinfunction "EN_3") (pintype "input"))
    )
    (net (code "64") (name "VUSB-RAW") (class "Default")
      (node (ref "C11") (pin "1") (pinfunction "1_1") (pintype "passive"))
      (node (ref "F1") (pin "1") (pinfunction "1_1") (pintype "bidirectional"))
      (node (ref "J1") (pin "2") (pinfunction "2_2") (pintype "passive"))
      (node (ref "J2") (pin "2") (pinfunction "2_2") (pintype "passive"))
      (node (ref "JP15") (pin "VBUS") (pinfunction "VCC_VBUS") (pintype "bidirectional"))
    )
    (net (code "65") (name "V_BATT") (class "Default")
      (node (ref "C6") (pin "1") (pinfunction "1_1") (pintype "passive"))
      (node (ref "J1") (pin "3") (pinfunction "3_3") (pintype "passive"))
      (node (ref "J2") (pin "3") (pinfunction "3_3") (pintype "passive"))
      (node (ref "JP2") (pin "2") (pinfunction "2_2") (pintype "passive"))
      (node (ref "Q1") (pin "3") (pinfunction "D_3") (pintype "passive"))
      (node (ref "U1") (pin "3") (pinfunction "VBAT_3") (pintype "power_in"))
    )
    (net (code "66") (name "V_USB") (class "Default")
      (node (ref "C14") (pin "1") (pinfunction "1_1") (pintype "passive"))
      (node (ref "C15") (pin "1") (pinfunction "1_1") (pintype "passive"))
      (node (ref "C19") (pin "1") (pinfunction "1_1") (pintype "passive"))
      (node (ref "D2") (pin "A") (pinfunction "A_A") (pintype "passive"))
      (node (ref "F1") (pin "2") (pinfunction "2_2") (pintype "bidirectional"))
      (node (ref "Q1") (pin "1") (pinfunction "G_1") (pintype "passive"))
      (node (ref "R3") (pin "1") (pinfunction "1_1") (pintype "passive"))
      (node (ref "R7") (pin "2") (pinfunction "2_2") (pintype "passive"))
      (node (ref "U1") (pin "4") (pinfunction "VIN_4") (pintype "power_in"))
      (node (ref "U4") (pin "15") (pinfunction "VCC_15") (pintype "bidirectional"))
    )
    (net (code "67") (name "unconnected-(JP15-PadID)") (class "Default")
      (node (ref "JP15") (pin "ID") (pinfunction "ID_ID") (pintype "bidirectional"))
    )
    (net (code "68") (name "unconnected-(U3-BP-Pad4)") (class "Default")
      (node (ref "U3") (pin "4") (pinfunction "BP_4") (pintype "input"))
    )
    (net (code "69") (name "unconnected-(U4-CBUS0-Pad18)") (class "Default")
      (node (ref "U4") (pin "18") (pinfunction "CBUS0_18") (pintype "bidirectional"))
    )
    (net (code "70") (name "unconnected-(U4-CBUS1-Pad17)") (class "Default")
      (node (ref "U4") (pin "17") (pinfunction "CBUS1_17") (pintype "bidirectional"))
    )
    (net (code "71") (name "unconnected-(U4-CBUS2-Pad10)") (class "Default")
      (node (ref "U4") (pin "10") (pinfunction "CBUS2_10") (pintype "bidirectional"))
    )
    (net (code "72") (name "unconnected-(U4-CBUS3-Pad19)") (class "Default")
      (node (ref "U4") (pin "19") (pinfunction "CBUS3_19") (pintype "bidirectional"))
    )
    (net (code "73") (name "unconnected-(U4-~{CTS}-Pad9)") (class "Default")
      (node (ref "U4") (pin "9") (pinfunction "~{CTS}_9") (pintype "bidirectional"))
    )
    (net (code "74") (name "unconnected-(U4-~{DCD}-Pad8)") (class "Default")
      (node (ref "U4") (pin "8") (pinfunction "~{DCD}_8") (pintype "bidirectional"))
    )
    (net (code "75") (name "unconnected-(U4-~{DSR}-Pad7)") (class "Default")
      (node (ref "U4") (pin "7") (pinfunction "~{DSR}_7") (pintype "bidirectional"))
    )
    (net (code "76") (name "unconnected-(U4-~{RI}-Pad5)") (class "Default")
      (node (ref "U4") (pin "5") (pinfunction "~{RI}_5") (pintype "bidirectional"))
    )
  )
)
